# Power.net
KiCad netlist of a schematic drawn in Altium Designer
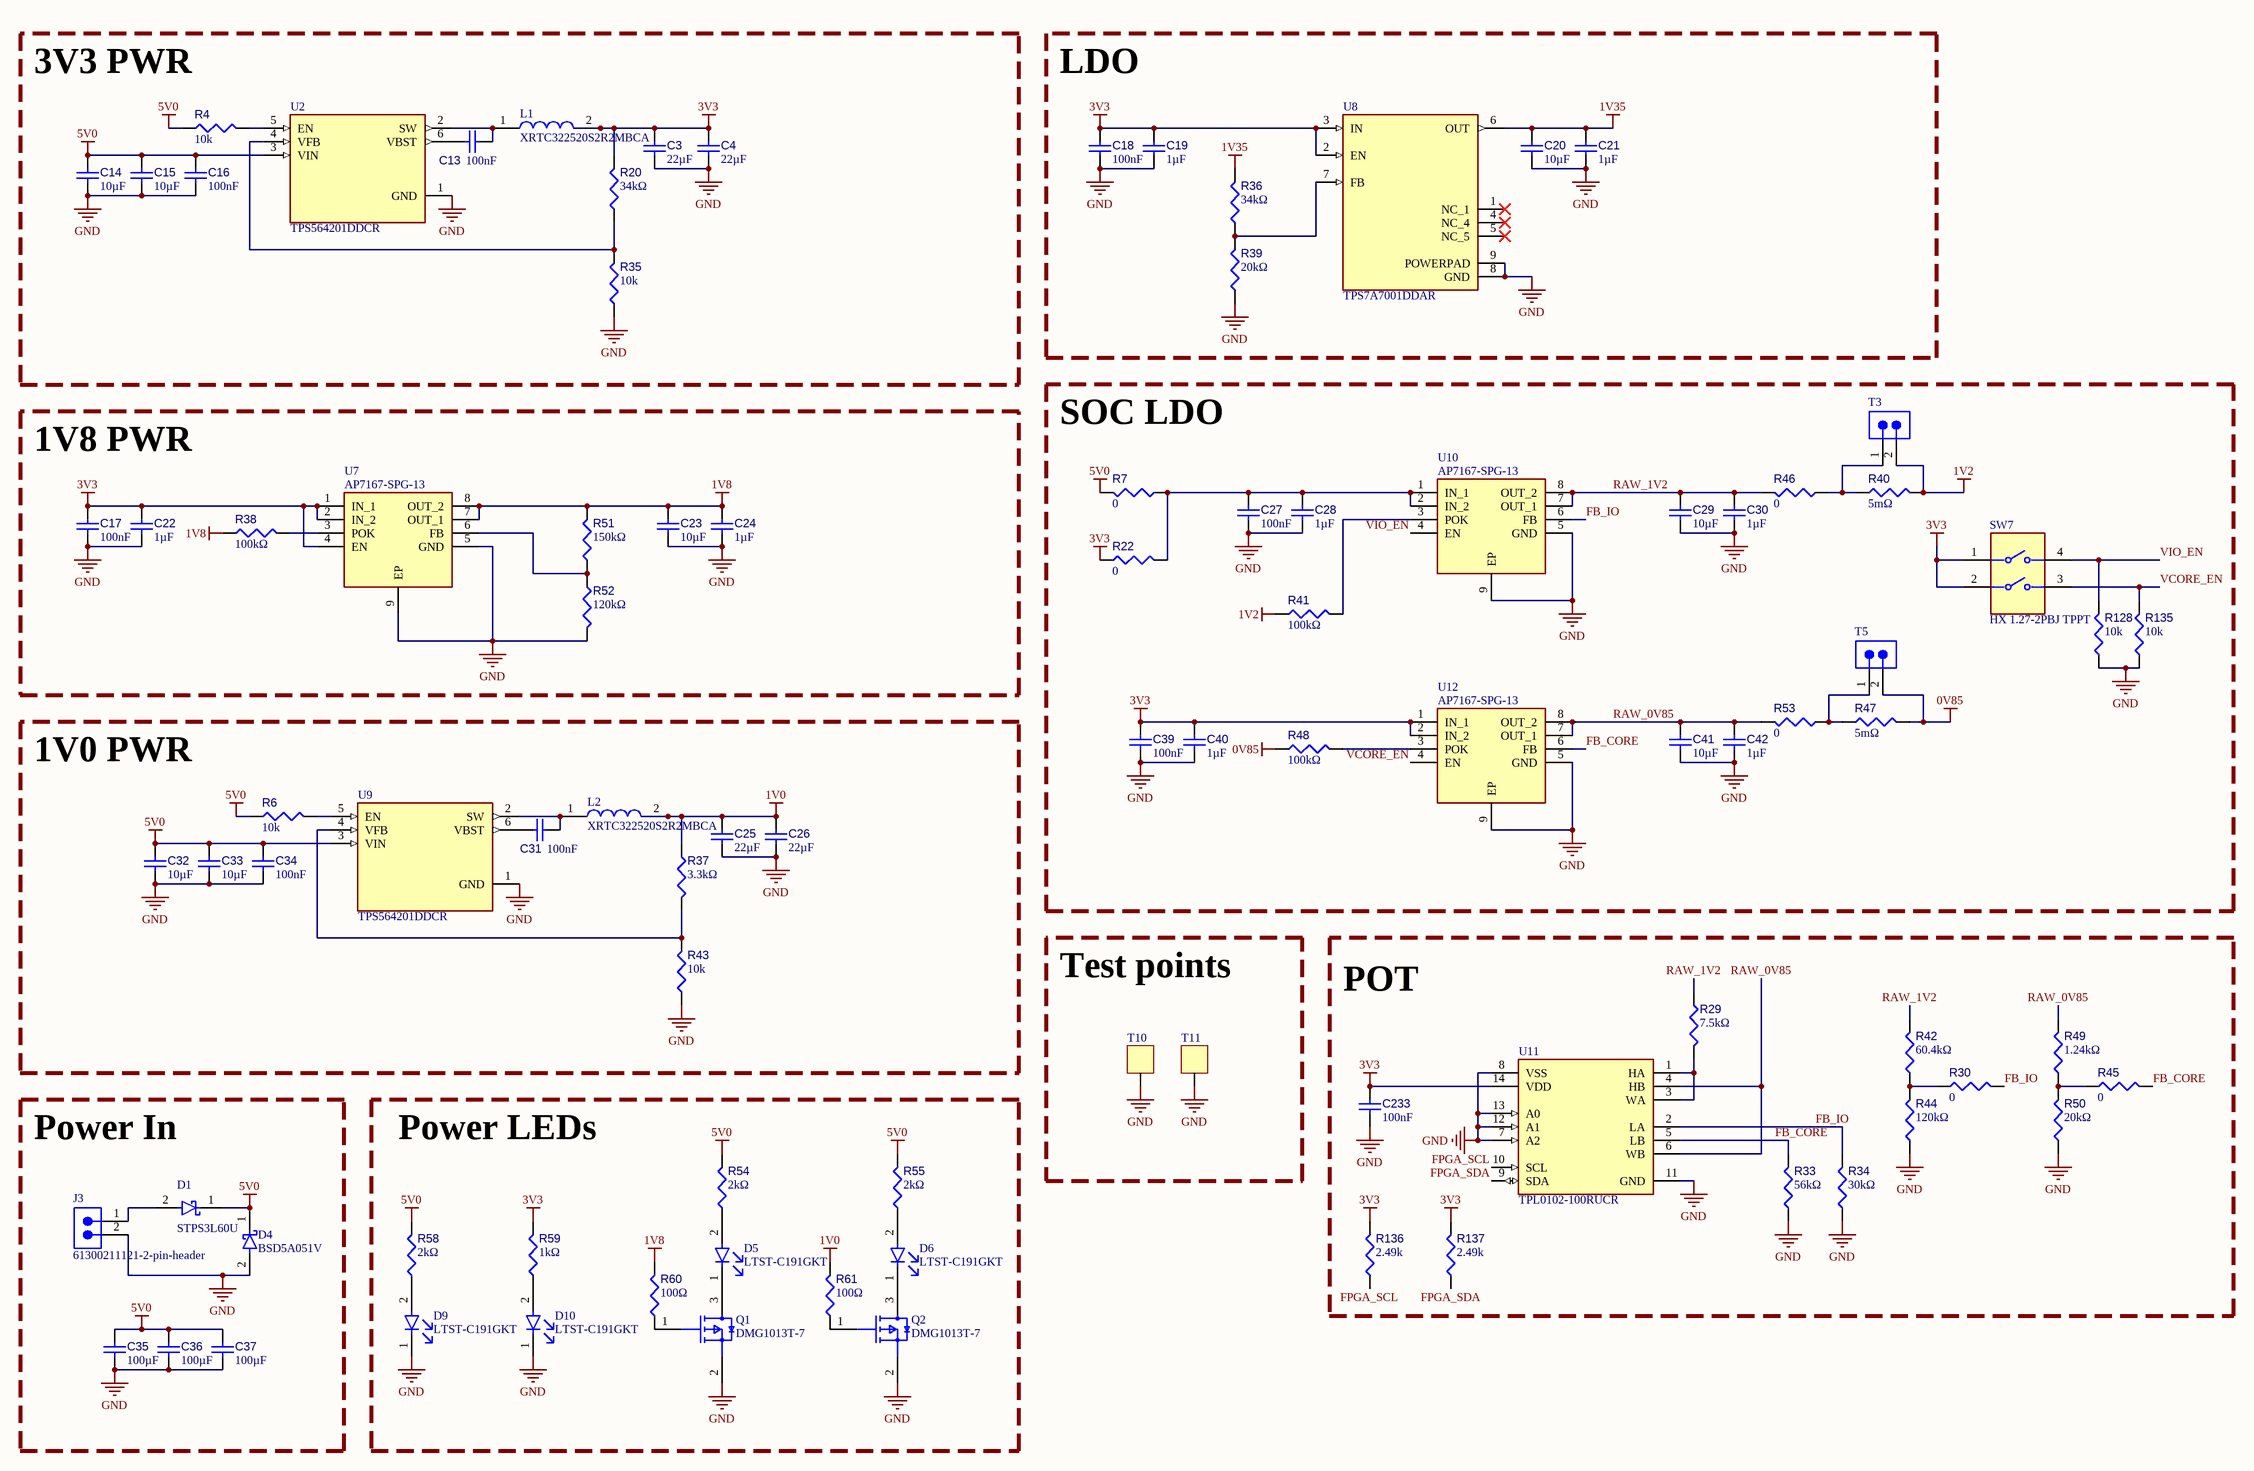
[diagram p0: Power.SchDoc]

(export (version "E")
  (design (tool "Eeschema 10.0.6"))
  (components
    (comp (ref "C3")
      (value "22µF")
      (footprint "CAP-0603-MFG")
      (description "0603-22u-20%-16V-X5R")
      (fields (field (name "TOLERANCE") "20%") (field (name "MANUFACTURER PART NUMBER") "CL10A226MO7JZNC"))
      (libsource (lib "UC Berkeley – EE194") (part "CAP-NP-2P"))
    )
    (comp (ref "C4")
      (value "22µF")
      (footprint "CAP-0603-MFG")
      (description "0603-22u-20%-16V-X5R")
      (fields (field (name "TOLERANCE") "20%") (field (name "MANUFACTURER PART NUMBER") "CL10A226MO7JZNC"))
      (libsource (lib "UC Berkeley – EE194") (part "CAP-NP-2P"))
    )
    (comp (ref "C13")
      (value "100nF")
      (footprint "CAP-0402-MFG")
      (description "0402-100n-10%-25V-X7R-AECQ200")
      (fields (field (name "TOLERANCE") "10%") (field (name "MANUFACTURER PART NUMBER") "CL05B104KA54PNC"))
      (libsource (lib "UC Berkeley – EE194") (part "CAP-NP-2P"))
    )
    (comp (ref "C14")
      (value "10µF")
      (footprint "CAP-0402-MFG")
      (description "0402-10u-20%-10V-X5R")
      (fields (field (name "TOLERANCE") "20%") (field (name "MANUFACTURER PART NUMBER") "CL05A106MP5NUNC"))
      (libsource (lib "UC Berkeley – EE194") (part "CAP-NP-2P"))
    )
    (comp (ref "C15")
      (value "10µF")
      (footprint "CAP-0402-MFG")
      (description "0402-10u-20%-10V-X5R")
      (fields (field (name "TOLERANCE") "20%") (field (name "MANUFACTURER PART NUMBER") "CL05A106MP5NUNC"))
      (libsource (lib "UC Berkeley – EE194") (part "CAP-NP-2P"))
    )
    (comp (ref "C16")
      (value "100nF")
      (footprint "CAP-0402-MFG")
      (description "0402-100n-10%-25V-X7R-AECQ200")
      (fields (field (name "TOLERANCE") "10%") (field (name "MANUFACTURER PART NUMBER") "CL05B104KA54PNC"))
      (libsource (lib "UC Berkeley – EE194") (part "CAP-NP-2P"))
    )
    (comp (ref "C17")
      (value "100nF")
      (footprint "CAP-0402-MFG")
      (description "0402-100n-10%-25V-X7R-AECQ200")
      (fields (field (name "TOLERANCE") "10%") (field (name "MANUFACTURER PART NUMBER") "CL05B104KA54PNC"))
      (libsource (lib "UC Berkeley – EE194") (part "CAP-NP-2P"))
    )
    (comp (ref "C18")
      (value "100nF")
      (footprint "CAP-0402-MFG")
      (description "0402-100n-10%-25V-X7R-AECQ200")
      (fields (field (name "TOLERANCE") "10%") (field (name "MANUFACTURER PART NUMBER") "CL05B104KA54PNC"))
      (libsource (lib "UC Berkeley – EE194") (part "CAP-NP-2P"))
    )
    (comp (ref "C19")
      (value "1µF")
      (footprint "CAP-0402-MFG")
      (description "0402-1u-10%-16V-X6S-AECQ200")
      (fields (field (name "MANUFACTURER PART NUMBER") "GRT155C81C105KE13J") (field (name "TOLERANCE") "10%"))
      (libsource (lib "UC Berkeley – EE194") (part "CAP-NP-2P"))
    )
    (comp (ref "C20")
      (value "10µF")
      (footprint "CAP-0402-MFG")
      (description "0402-10u-20%-10V-X5R")
      (fields (field (name "TOLERANCE") "20%") (field (name "MANUFACTURER PART NUMBER") "CL05A106MP5NUNC"))
      (libsource (lib "UC Berkeley – EE194") (part "CAP-NP-2P"))
    )
    (comp (ref "C21")
      (value "1µF")
      (footprint "CAP-0402-MFG")
      (description "0402-1u-10%-16V-X6S-AECQ200")
      (fields (field (name "MANUFACTURER PART NUMBER") "GRT155C81C105KE13J") (field (name "TOLERANCE") "10%"))
      (libsource (lib "UC Berkeley – EE194") (part "CAP-NP-2P"))
    )
    (comp (ref "C22")
      (value "1µF")
      (footprint "CAP-0402-MFG")
      (description "0402-1u-10%-16V-X6S-AECQ200")
      (fields (field (name "MANUFACTURER PART NUMBER") "GRT155C81C105KE13J") (field (name "TOLERANCE") "10%"))
      (libsource (lib "UC Berkeley – EE194") (part "CAP-NP-2P"))
    )
    (comp (ref "C23")
      (value "10µF")
      (footprint "CAP-0402-MFG")
      (description "0402-10u-20%-10V-X5R")
      (fields (field (name "TOLERANCE") "20%") (field (name "MANUFACTURER PART NUMBER") "CL05A106MP5NUNC"))
      (libsource (lib "UC Berkeley – EE194") (part "CAP-NP-2P"))
    )
    (comp (ref "C24")
      (value "1µF")
      (footprint "CAP-0402-MFG")
      (description "0402-1u-10%-16V-X6S-AECQ200")
      (fields (field (name "MANUFACTURER PART NUMBER") "GRT155C81C105KE13J") (field (name "TOLERANCE") "10%"))
      (libsource (lib "UC Berkeley – EE194") (part "CAP-NP-2P"))
    )
    (comp (ref "C25")
      (value "22µF")
      (footprint "CAP-0603-MFG")
      (description "0603-22u-20%-16V-X5R")
      (fields (field (name "TOLERANCE") "20%") (field (name "MANUFACTURER PART NUMBER") "CL10A226MO7JZNC"))
      (libsource (lib "UC Berkeley – EE194") (part "CAP-NP-2P"))
    )
    (comp (ref "C26")
      (value "22µF")
      (footprint "CAP-0603-MFG")
      (description "0603-22u-20%-16V-X5R")
      (fields (field (name "TOLERANCE") "20%") (field (name "MANUFACTURER PART NUMBER") "CL10A226MO7JZNC"))
      (libsource (lib "UC Berkeley – EE194") (part "CAP-NP-2P"))
    )
    (comp (ref "C27")
      (value "100nF")
      (footprint "CAP-0402-MFG")
      (description "0402-100n-10%-25V-X7R-AECQ200")
      (fields (field (name "TOLERANCE") "10%") (field (name "MANUFACTURER PART NUMBER") "CL05B104KA54PNC"))
      (libsource (lib "UC Berkeley – EE194") (part "CAP-NP-2P"))
    )
    (comp (ref "C28")
      (value "1µF")
      (footprint "CAP-0402-MFG")
      (description "0402-1u-10%-16V-X6S-AECQ200")
      (fields (field (name "MANUFACTURER PART NUMBER") "GRT155C81C105KE13J") (field (name "TOLERANCE") "10%"))
      (libsource (lib "UC Berkeley – EE194") (part "CAP-NP-2P"))
    )
    (comp (ref "C29")
      (value "10µF")
      (footprint "CAP-0402-MFG")
      (description "0402-10u-20%-10V-X5R")
      (fields (field (name "TOLERANCE") "20%") (field (name "MANUFACTURER PART NUMBER") "CL05A106MP5NUNC"))
      (libsource (lib "UC Berkeley – EE194") (part "CAP-NP-2P"))
    )
    (comp (ref "C30")
      (value "1µF")
      (footprint "CAP-0402-MFG")
      (description "0402-1u-10%-16V-X6S-AECQ200")
      (fields (field (name "MANUFACTURER PART NUMBER") "GRT155C81C105KE13J") (field (name "TOLERANCE") "10%"))
      (libsource (lib "UC Berkeley – EE194") (part "CAP-NP-2P"))
    )
    (comp (ref "C31")
      (value "100nF")
      (footprint "CAP-0402-MFG")
      (description "0402-100n-10%-25V-X7R-AECQ200")
      (fields (field (name "TOLERANCE") "10%") (field (name "MANUFACTURER PART NUMBER") "CL05B104KA54PNC"))
      (libsource (lib "UC Berkeley – EE194") (part "CAP-NP-2P"))
    )
    (comp (ref "C32")
      (value "10µF")
      (footprint "CAP-0402-MFG")
      (description "0402-10u-20%-10V-X5R")
      (fields (field (name "TOLERANCE") "20%") (field (name "MANUFACTURER PART NUMBER") "CL05A106MP5NUNC"))
      (libsource (lib "UC Berkeley – EE194") (part "CAP-NP-2P"))
    )
    (comp (ref "C33")
      (value "10µF")
      (footprint "CAP-0402-MFG")
      (description "0402-10u-20%-10V-X5R")
      (fields (field (name "TOLERANCE") "20%") (field (name "MANUFACTURER PART NUMBER") "CL05A106MP5NUNC"))
      (libsource (lib "UC Berkeley – EE194") (part "CAP-NP-2P"))
    )
    (comp (ref "C34")
      (value "100nF")
      (footprint "CAP-0402-MFG")
      (description "0402-100n-10%-25V-X7R-AECQ200")
      (fields (field (name "TOLERANCE") "10%") (field (name "MANUFACTURER PART NUMBER") "CL05B104KA54PNC"))
      (libsource (lib "UC Berkeley – EE194") (part "CAP-NP-2P"))
    )
    (comp (ref "C35")
      (value "100µF")
      (footprint "CAP-0805-MFG")
      (description "0805-100u-20%-6.3V-X5R")
      (fields (field (name "MANUFACTURER PART NUMBER") "GRM21BR60J107ME15L") (field (name "TOLERANCE") "20%"))
      (libsource (lib "UC Berkeley – EE194") (part "CAP-NP-2P"))
    )
    (comp (ref "C36")
      (value "100µF")
      (footprint "CAP-0805-MFG")
      (description "0805-100u-20%-6.3V-X5R")
      (fields (field (name "MANUFACTURER PART NUMBER") "GRM21BR60J107ME15L") (field (name "TOLERANCE") "20%"))
      (libsource (lib "UC Berkeley – EE194") (part "CAP-NP-2P"))
    )
    (comp (ref "C37")
      (value "100µF")
      (footprint "CAP-0805-MFG")
      (description "0805-100u-20%-6.3V-X5R")
      (fields (field (name "MANUFACTURER PART NUMBER") "GRM21BR60J107ME15L") (field (name "TOLERANCE") "20%"))
      (libsource (lib "UC Berkeley – EE194") (part "CAP-NP-2P"))
    )
    (comp (ref "C39")
      (value "100nF")
      (footprint "CAP-0402-MFG")
      (description "0402-100n-10%-25V-X7R-AECQ200")
      (fields (field (name "TOLERANCE") "10%") (field (name "MANUFACTURER PART NUMBER") "CL05B104KA54PNC"))
      (libsource (lib "UC Berkeley – EE194") (part "CAP-NP-2P"))
    )
    (comp (ref "C40")
      (value "1µF")
      (footprint "CAP-0402-MFG")
      (description "0402-1u-10%-16V-X6S-AECQ200")
      (fields (field (name "MANUFACTURER PART NUMBER") "GRT155C81C105KE13J") (field (name "TOLERANCE") "10%"))
      (libsource (lib "UC Berkeley – EE194") (part "CAP-NP-2P"))
    )
    (comp (ref "C41")
      (value "10µF")
      (footprint "CAP-0402-MFG")
      (description "0402-10u-20%-10V-X5R")
      (fields (field (name "TOLERANCE") "20%") (field (name "MANUFACTURER PART NUMBER") "CL05A106MP5NUNC"))
      (libsource (lib "UC Berkeley – EE194") (part "CAP-NP-2P"))
    )
    (comp (ref "C42")
      (value "1µF")
      (footprint "CAP-0402-MFG")
      (description "0402-1u-10%-16V-X6S-AECQ200")
      (fields (field (name "MANUFACTURER PART NUMBER") "GRT155C81C105KE13J") (field (name "TOLERANCE") "10%"))
      (libsource (lib "UC Berkeley – EE194") (part "CAP-NP-2P"))
    )
    (comp (ref "C233")
      (value "100nF")
      (footprint "CAP-0402-MFG")
      (description "0402-100n-10%-25V-X7R-AECQ200")
      (fields (field (name "TOLERANCE") "10%") (field (name "MANUFACTURER PART NUMBER") "CL05B104KA54PNC"))
      (libsource (lib "UC Berkeley – EE194") (part "CAP-NP-2P"))
    )
    (comp (ref "D1")
      (value "STPS3L60U")
      (footprint "FP-DO214AA-MFG")
      (description "DO214AA-UNI-SCHOTTKY-60V-3A-590mV")
      (libsource (lib "UC Berkeley – EE194") (part "SCHOTTKY-UNI-2P-DIODE"))
    )
    (comp (ref "D4")
      (value "BSD5A051V")
      (footprint "SOD-523")
      (description "TVS ESD protection clamp generic")
      (fields (field (name "SOURCE") "BWRC.SchLib"))
      (libsource (lib "UC Berkeley – EE194") (part "SCHOTTKY-UNI-2P-DIODE"))
    )
    (comp (ref "D5")
      (value "LTST-C191GKT")
      (footprint "LED-0603-MFG")
      (description "LED yellow green 0603 wavelength 569nm light intensity 12mcd Front Mounting")
      (libsource (lib "UC Berkeley – EE194") (part "LED"))
    )
    (comp (ref "D6")
      (value "LTST-C191GKT")
      (footprint "LED-0603-MFG")
      (description "LED yellow green 0603 wavelength 569nm light intensity 12mcd Front Mounting")
      (libsource (lib "UC Berkeley – EE194") (part "LED"))
    )
    (comp (ref "D9")
      (value "LTST-C191GKT")
      (footprint "LED-0603-MFG")
      (description "LED yellow green 0603 wavelength 569nm light intensity 12mcd Front Mounting")
      (libsource (lib "UC Berkeley – EE194") (part "LED"))
    )
    (comp (ref "D10")
      (value "LTST-C191GKT")
      (footprint "LED-0603-MFG")
      (description "LED yellow green 0603 wavelength 569nm light intensity 12mcd Front Mounting")
      (libsource (lib "UC Berkeley – EE194") (part "LED"))
    )
    (comp (ref "J3")
      (value "61300211121-2-pin-header")
      (footprint "61300211121")
      (fields (field (name "MANUFACTURER PART NUMBER") "61300211121"))
      (libsource (lib "UC Berkeley – EE194") (part "Header_Male_1R_02P"))
    )
    (comp (ref "L1")
      (value "XRTC322520S2R2MBCA")
      (footprint "INDC2520X100N")
      (description "Ind,3.2x2.5x1mm,2.2uH?20%,4A,shd")
      (libsource (lib "UC Berkeley – EE194") (part "XRTC322520S2R2MBCA"))
    )
    (comp (ref "L2")
      (value "XRTC322520S2R2MBCA")
      (footprint "INDC2520X100N")
      (description "Ind,3.2x2.5x1mm,2.2uH?20%,4A,shd")
      (libsource (lib "UC Berkeley – EE194") (part "XRTC322520S2R2MBCA"))
    )
    (comp (ref "Q1")
      (value "DMG1013T-7")
      (footprint "FP-SOT523-MFG")
      (description "P-Channel 20 V 0.7 Ohm 0.27 W Enhancement Mode Mosfet - SOT-523")
      (libsource (lib "UC Berkeley – EE194") (part "P-MOSFET-3P"))
    )
    (comp (ref "Q2")
      (value "DMG1013T-7")
      (footprint "FP-SOT523-MFG")
      (description "P-Channel 20 V 0.7 Ohm 0.27 W Enhancement Mode Mosfet - SOT-523")
      (libsource (lib "UC Berkeley – EE194") (part "P-MOSFET-3P"))
    )
    (comp (ref "R4")
      (value "10k")
      (footprint "RES-0402")
      (description "0402-10k-1%-1/16W-AEC-Q200")
      (fields (field (name "POWER") "63mW") (field (name "TOLERANCE") "1%"))
      (libsource (lib "UC Berkeley – EE194") (part "RES-2P"))
    )
    (comp (ref "R6")
      (value "10k")
      (footprint "RES-0402")
      (description "0402-10k-1%-1/16W-AEC-Q200")
      (fields (field (name "POWER") "63mW") (field (name "TOLERANCE") "1%"))
      (libsource (lib "UC Berkeley – EE194") (part "RES-2P"))
    )
    (comp (ref "R7")
      (value "0")
      (footprint "RES-0402")
      (description "0402-0-1A-AEC-Q200")
      (fields (field (name "MANUFACTURER PART NUMBER") "AC0402JR-130RL"))
      (libsource (lib "UC Berkeley – EE194") (part "RES-2P"))
    )
    (comp (ref "R20")
      (value "34kΩ")
      (footprint "RES-0402")
      (description "0402-34k-1%-1/16W-AEC-Q200")
      (fields (field (name "TOLERANCE") "1%") (field (name "POWER") "63mW"))
      (libsource (lib "UC Berkeley – EE194") (part "RES-2P"))
    )
    (comp (ref "R22")
      (value "0")
      (footprint "RES-0402")
      (description "0402-0-1A-AEC-Q200")
      (fields (field (name "MANUFACTURER PART NUMBER") "AC0402JR-130RL"))
      (libsource (lib "UC Berkeley – EE194") (part "RES-2P"))
    )
    (comp (ref "R29")
      (value "7.5kΩ")
      (footprint "RES-0402")
      (description "0402-7.5k-1%-1/16W-AEC-Q200")
      (fields (field (name "TOLERANCE") "1%") (field (name "MANUFACTURER PART NUMBER") "CRCW04027K50FKED"))
      (libsource (lib "UC Berkeley – EE194") (part "RES-2P"))
    )
    (comp (ref "R30")
      (value "0")
      (footprint "RES-0402")
      (description "0402-0-1A-AEC-Q200")
      (fields (field (name "MANUFACTURER PART NUMBER") "AC0402JR-130RL"))
      (libsource (lib "UC Berkeley – EE194") (part "RES-2P"))
    )
    (comp (ref "R33")
      (value "56kΩ")
      (footprint "RES-0402")
      (description "0402-56k-1%-1/16W-AEC-Q200")
      (fields (field (name "TOLERANCE") "1%") (field (name "MANUFACTURER PART NUMBER") "AF0402FR-0756KL"))
      (libsource (lib "UC Berkeley – EE194") (part "RES-2P"))
    )
    (comp (ref "R34")
      (value "30kΩ")
      (footprint "RES-0402")
      (description "0402-30k-1%-1/16W-AEC-Q200")
      (fields (field (name "TOLERANCE") "1%") (field (name "POWER") "63mW"))
      (libsource (lib "UC Berkeley – EE194") (part "RES-2P"))
    )
    (comp (ref "R35")
      (value "10k")
      (footprint "RES-0402")
      (description "0402-10k-1%-1/16W-AEC-Q200")
      (fields (field (name "POWER") "63mW") (field (name "TOLERANCE") "1%"))
      (libsource (lib "UC Berkeley – EE194") (part "RES-2P"))
    )
    (comp (ref "R36")
      (value "34kΩ")
      (footprint "RES-0402")
      (description "0402-34k-1%-1/16W-AEC-Q200")
      (fields (field (name "TOLERANCE") "1%") (field (name "POWER") "63mW"))
      (libsource (lib "UC Berkeley – EE194") (part "RES-2P"))
    )
    (comp (ref "R37")
      (value "3.3kΩ")
      (footprint "RES-0402")
      (description "0402-3.3k-1%-1/16W-AEC-Q200")
      (fields (field (name "POWER") "63mW") (field (name "TOLERANCE") "1%"))
      (libsource (lib "UC Berkeley – EE194") (part "RES-2P"))
    )
    (comp (ref "R38")
      (value "100kΩ")
      (footprint "RES-0402")
      (description "0402-100k-1%-1/16W-AEC-Q200")
      (fields (field (name "MANUFACTURER PART NUMBER") "AC0402FR-07100KL") (field (name "TOLERANCE") "1%"))
      (libsource (lib "UC Berkeley – EE194") (part "RES-2P"))
    )
    (comp (ref "R39")
      (value "20kΩ")
      (footprint "RES-0402")
      (description "0402-20k-1%-1/16W-AEC-Q200")
      (fields (field (name "TOLERANCE") "1%") (field (name "MANUFACTURER PART NUMBER") "AC0402FR-0720KL"))
      (libsource (lib "UC Berkeley – EE194") (part "RES-2P"))
    )
    (comp (ref "R40")
      (value "5mΩ")
      (footprint "RES-0603-MFG")
      (description "0603-5m-1%-0.5W-AECQ200")
      (fields (field (name "TOLERANCE") "1%") (field (name "MANUFACTURER PART NUMBER") "PA0603FRE570R005L"))
      (libsource (lib "UC Berkeley – EE194") (part "RES-2P"))
    )
    (comp (ref "R41")
      (value "100kΩ")
      (footprint "RES-0402")
      (description "0402-100k-1%-1/16W-AEC-Q200")
      (fields (field (name "MANUFACTURER PART NUMBER") "AC0402FR-07100KL") (field (name "TOLERANCE") "1%"))
      (libsource (lib "UC Berkeley – EE194") (part "RES-2P"))
    )
    (comp (ref "R42")
      (value "60.4kΩ")
      (footprint "RES-0402")
      (description "0402-60.4k-1%-1/16W-AEC-Q200")
      (fields (field (name "TOLERANCE") "1%") (field (name "MANUFACTURER PART NUMBER") "AC0402FR-0760K4L"))
      (libsource (lib "UC Berkeley – EE194") (part "RES-2P"))
    )
    (comp (ref "R43")
      (value "10k")
      (footprint "RES-0402")
      (description "0402-10k-1%-1/16W-AEC-Q200")
      (fields (field (name "POWER") "63mW") (field (name "TOLERANCE") "1%"))
      (libsource (lib "UC Berkeley – EE194") (part "RES-2P"))
    )
    (comp (ref "R44")
      (value "120kΩ")
      (footprint "RES-0402")
      (description "0402-120k-1%-1/16W-AEC-Q200")
      (fields (field (name "POWER") "63mW") (field (name "MANUFACTURER PART NUMBER") "AC0402FR-07120KL"))
      (libsource (lib "UC Berkeley – EE194") (part "RES-2P"))
    )
    (comp (ref "R45")
      (value "0")
      (footprint "RES-0402")
      (description "0402-0-1A-AEC-Q200")
      (fields (field (name "MANUFACTURER PART NUMBER") "AC0402JR-130RL"))
      (libsource (lib "UC Berkeley – EE194") (part "RES-2P"))
    )
    (comp (ref "R46")
      (value "0")
      (footprint "RES-0603-MFG")
      (description "0603-0-1A-AECQ200")
      (fields (field (name "MANUFACTURER PART NUMBER") "AC0603FR-070RL") (field (name "TOLERANCE") "1%"))
      (libsource (lib "UC Berkeley – EE194") (part "RES-2P"))
    )
    (comp (ref "R47")
      (value "5mΩ")
      (footprint "RES-0603-MFG")
      (description "0603-5m-1%-0.5W-AECQ200")
      (fields (field (name "TOLERANCE") "1%") (field (name "MANUFACTURER PART NUMBER") "PA0603FRE570R005L"))
      (libsource (lib "UC Berkeley – EE194") (part "RES-2P"))
    )
    (comp (ref "R48")
      (value "100kΩ")
      (footprint "RES-0402")
      (description "0402-100k-1%-1/16W-AEC-Q200")
      (fields (field (name "MANUFACTURER PART NUMBER") "AC0402FR-07100KL") (field (name "TOLERANCE") "1%"))
      (libsource (lib "UC Berkeley – EE194") (part "RES-2P"))
    )
    (comp (ref "R49")
      (value "1.24kΩ")
      (footprint "RES-0402")
      (description "0402-1.24k-1%-1/16W-AEC-Q200")
      (fields (field (name "POWER") "63mW") (field (name "TOLERANCE") "1%"))
      (libsource (lib "UC Berkeley – EE194") (part "RES-2P"))
    )
    (comp (ref "R50")
      (value "20kΩ")
      (footprint "RES-0402")
      (description "0402-20k-1%-1/16W-AEC-Q200")
      (fields (field (name "MANUFACTURER PART NUMBER") "AC0402FR-0720KL") (field (name "TOLERANCE") "1%"))
      (libsource (lib "UC Berkeley – EE194") (part "RES-2P"))
    )
    (comp (ref "R51")
      (value "150kΩ")
      (footprint "RES-0402")
      (description "0402-150k-1%-1/16W-AEC-Q200")
      (fields (field (name "POWER") "63mW") (field (name "TOLERANCE") "1%"))
      (libsource (lib "UC Berkeley – EE194") (part "RES-2P"))
    )
    (comp (ref "R52")
      (value "120kΩ")
      (footprint "RES-0402")
      (description "0402-120k-1%-1/16W-AEC-Q200")
      (fields (field (name "POWER") "63mW") (field (name "MANUFACTURER PART NUMBER") "AC0402FR-07120KL"))
      (libsource (lib "UC Berkeley – EE194") (part "RES-2P"))
    )
    (comp (ref "R53")
      (value "0")
      (footprint "RES-0603-MFG")
      (description "0603-0-1A-AECQ200")
      (fields (field (name "MANUFACTURER PART NUMBER") "AC0603FR-070RL") (field (name "TOLERANCE") "1%"))
      (libsource (lib "UC Berkeley – EE194") (part "RES-2P"))
    )
    (comp (ref "R54")
      (value "2kΩ")
      (footprint "RES-0402")
      (description "0402-2k-1%-1/16W-AEC-Q200")
      (fields (field (name "TOLERANCE") "1%") (field (name "POWER") "63mW"))
      (libsource (lib "UC Berkeley – EE194") (part "RES-2P"))
    )
    (comp (ref "R55")
      (value "2kΩ")
      (footprint "RES-0402")
      (description "0402-2k-1%-1/16W-AEC-Q200")
      (fields (field (name "TOLERANCE") "1%") (field (name "POWER") "63mW"))
      (libsource (lib "UC Berkeley – EE194") (part "RES-2P"))
    )
    (comp (ref "R58")
      (value "2kΩ")
      (footprint "RES-0402")
      (description "0402-2k-1%-1/16W-AEC-Q200")
      (fields (field (name "TOLERANCE") "1%") (field (name "POWER") "63mW"))
      (libsource (lib "UC Berkeley – EE194") (part "RES-2P"))
    )
    (comp (ref "R59")
      (value "1kΩ")
      (footprint "RES-0402")
      (description "0402-1k-1%-1/16W-AEC-Q200")
      (fields (field (name "MANUFACTURER PART NUMBER") "AC0402FR-071KL") (field (name "POWER") "63mW"))
      (libsource (lib "UC Berkeley – EE194") (part "RES-2P"))
    )
    (comp (ref "R60")
      (value "100Ω")
      (footprint "RES-0402")
      (description "0402-100-1%-1/16W-AEC-Q200")
      (fields (field (name "MANUFACTURER PART NUMBER") "AC0402FR-07100RL") (field (name "POWER") "63mW"))
      (libsource (lib "UC Berkeley – EE194") (part "RES-2P"))
    )
    (comp (ref "R61")
      (value "100Ω")
      (footprint "RES-0402")
      (description "0402-100-1%-1/16W-AEC-Q200")
      (fields (field (name "MANUFACTURER PART NUMBER") "AC0402FR-07100RL") (field (name "POWER") "63mW"))
      (libsource (lib "UC Berkeley – EE194") (part "RES-2P"))
    )
    (comp (ref "R128")
      (value "10k")
      (footprint "RES-0402")
      (description "0402-10k-1%-1/16W-AEC-Q200")
      (fields (field (name "TOLERANCE") "1%") (field (name "MANUFACTURER PART NUMBER") "AC0402FR-0710KL"))
      (libsource (lib "UC Berkeley – EE194") (part "RES-2P"))
    )
    (comp (ref "R135")
      (value "10k")
      (footprint "RES-0402")
      (description "0402-10k-1%-1/16W-AEC-Q200")
      (fields (field (name "TOLERANCE") "1%") (field (name "MANUFACTURER PART NUMBER") "AC0402FR-0710KL"))
      (libsource (lib "UC Berkeley – EE194") (part "RES-2P"))
    )
    (comp (ref "R136")
      (value "2.49k")
      (footprint "RES-0402")
      (description "0402-2.49k-1%-1/16W-AECQ200")
      (fields (field (name "TOLERANCE") "1%") (field (name "MANUFACTURER PART NUMBER") "AC0402FR-072K49L"))
      (libsource (lib "UC Berkeley – EE194") (part "RES-2P"))
    )
    (comp (ref "R137")
      (value "2.49k")
      (footprint "RES-0402")
      (description "0402-2.49k-1%-1/16W-AECQ200")
      (fields (field (name "TOLERANCE") "1%") (field (name "MANUFACTURER PART NUMBER") "AC0402FR-072K49L"))
      (libsource (lib "UC Berkeley – EE194") (part "RES-2P"))
    )
    (comp (ref "SW7")
      (value "HX 1.27-2PBJ TPPT")
      (footprint "HX 1.27-2PBJ TPPT-Footprint-1")
      (description "Dual 1.27mm SMT DIP Switch")
      (libsource (lib "UC Berkeley – EE194") (part "HX 1.27-2PBJ TPPT-Symbol-1"))
    )
    (comp (ref "T3")
      (value "61300211121-2-pin-header")
      (footprint "61300211121")
      (fields (field (name "MANUFACTURER PART NUMBER") "61300211121"))
      (libsource (lib "UC Berkeley – EE194") (part "Header_Male_1R_02P"))
    )
    (comp (ref "T5")
      (value "61300211121-2-pin-header")
      (footprint "61300211121")
      (fields (field (name "MANUFACTURER PART NUMBER") "61300211121"))
      (libsource (lib "UC Berkeley – EE194") (part "Header_Male_1R_02P"))
    )
    (comp (ref "T10")
      (value "TEST_PT")
      (footprint "TP-100X100/ROUND-THT")
      (description "Test point 1 pin")
      (fields (field (name "SOURCE") "BWRC.SchLib"))
      (libsource (lib "UC Berkeley – EE194") (part "TEST_PT"))
    )
    (comp (ref "T11")
      (value "TEST_PT")
      (footprint "TP-100X100/ROUND-THT")
      (description "Test point 1 pin")
      (fields (field (name "SOURCE") "BWRC.SchLib"))
      (libsource (lib "UC Berkeley – EE194") (part "TEST_PT"))
    )
    (comp (ref "U2")
      (value "TPS564201DDCR")
      (footprint "SOT95P280X110-6N")
      (libsource (lib "UC Berkeley – EE194") (part "TPS564201DDCR"))
    )
    (comp (ref "U7")
      (value "AP7167-SPG-13")
      (footprint "SOIC127P600X175-9N")
      (description "AP7167 Series 5.5 V 1.2 A Low Dropout Regulator with Pok - SOP-8EP")
      (libsource (lib "UC Berkeley – EE194") (part "AP7167-SPG-13"))
    )
    (comp (ref "U8")
      (value "TPS7A7001DDAR")
      (footprint "VREG_TPS7A7001DDAR")
      (description "2-A, adjustable ultra-low-dropout voltage regulator with enable")
      (libsource (lib "UC Berkeley – EE194") (part "TPS7A7001DDAR"))
    )
    (comp (ref "U9")
      (value "TPS564201DDCR")
      (footprint "SOT95P280X110-6N")
      (libsource (lib "UC Berkeley – EE194") (part "TPS564201DDCR"))
    )
    (comp (ref "U10")
      (value "AP7167-SPG-13")
      (footprint "SOIC127P600X175-9N")
      (description "AP7167 Series 5.5 V 1.2 A Low Dropout Regulator with Pok - SOP-8EP")
      (libsource (lib "UC Berkeley – EE194") (part "AP7167-SPG-13"))
    )
    (comp (ref "U11")
      (value "TPL0102-100RUCR")
      (footprint "FP-RUC0014A-IPC_B")
      (description "Digital Potentiometer 100kOhm 256POS Non-Volatile Linear 14-Pin X2QFN T/R")
      (fields (field (name "TOLERANCE") "20%"))
      (libsource (lib "UC Berkeley – EE194") (part "TPL0102-100RUCR"))
    )
    (comp (ref "U12")
      (value "AP7167-SPG-13")
      (footprint "SOIC127P600X175-9N")
      (description "AP7167 Series 5.5 V 1.2 A Low Dropout Regulator with Pok - SOP-8EP")
      (libsource (lib "UC Berkeley – EE194") (part "AP7167-SPG-13"))
    )
  )
  (nets
    (net (code "1") (name "/FB_CORE") (class "Default")
      (node (ref "R33") (pin "2") (pinfunction "2_2") (pintype "passive"))
      (node (ref "R45") (pin "2") (pinfunction "2_2") (pintype "passive"))
      (node (ref "U11") (pin "5") (pinfunction "LB_5") (pintype "passive"))
      (node (ref "U12") (pin "6") (pinfunction "FB_6") (pintype "passive"))
    )
    (net (code "2") (name "/FB_IO") (class "Default")
      (node (ref "R30") (pin "2") (pinfunction "2_2") (pintype "passive"))
      (node (ref "R34") (pin "2") (pinfunction "2_2") (pintype "passive"))
      (node (ref "U10") (pin "6") (pinfunction "FB_6") (pintype "passive"))
      (node (ref "U11") (pin "2") (pinfunction "LA_2") (pintype "passive"))
    )
    (net (code "3") (name "/FPGA_SCL") (class "Default")
      (node (ref "R136") (pin "1") (pinfunction "1_1") (pintype "passive"))
      (node (ref "U11") (pin "10") (pinfunction "SCL_10") (pintype "input"))
    )
    (net (code "4") (name "/FPGA_SDA") (class "Default")
      (node (ref "R137") (pin "1") (pinfunction "1_1") (pintype "passive"))
      (node (ref "U11") (pin "9") (pinfunction "SDA_9") (pintype "bidirectional"))
    )
    (net (code "5") (name "/RAW_0V85") (class "Default")
      (node (ref "C41") (pin "1") (pinfunction "1_1") (pintype "passive"))
      (node (ref "C42") (pin "1") (pinfunction "1_1") (pintype "passive"))
      (node (ref "R49") (pin "2") (pinfunction "2_2") (pintype "passive"))
      (node (ref "R53") (pin "2") (pinfunction "2_2") (pintype "passive"))
      (node (ref "U11") (pin "4") (pinfunction "HB_4") (pintype "passive"))
      (node (ref "U11") (pin "6") (pinfunction "WB_6") (pintype "passive"))
      (node (ref "U12") (pin "7") (pinfunction "OUT_1_7") (pintype "passive"))
      (node (ref "U12") (pin "8") (pinfunction "OUT_2_8") (pintype "passive"))
    )
    (net (code "6") (name "/RAW_1V2") (class "Default")
      (node (ref "C29") (pin "1") (pinfunction "1_1") (pintype "passive"))
      (node (ref "C30") (pin "1") (pinfunction "1_1") (pintype "passive"))
      (node (ref "R29") (pin "1") (pinfunction "1_1") (pintype "passive"))
      (node (ref "R42") (pin "2") (pinfunction "2_2") (pintype "passive"))
      (node (ref "R46") (pin "2") (pinfunction "2_2") (pintype "passive"))
      (node (ref "U10") (pin "7") (pinfunction "OUT_1_7") (pintype "passive"))
      (node (ref "U10") (pin "8") (pinfunction "OUT_2_8") (pintype "passive"))
    )
    (net (code "7") (name "/VCORE_EN") (class "Default")
      (node (ref "R135") (pin "2") (pinfunction "2_2") (pintype "passive"))
      (node (ref "SW7") (pin "3") (pinfunction "3_3") (pintype "passive"))
      (node (ref "U12") (pin "4") (pinfunction "EN_4") (pintype "passive"))
    )
    (net (code "8") (name "/VIO_EN") (class "Default")
      (node (ref "R128") (pin "2") (pinfunction "2_2") (pintype "passive"))
      (node (ref "SW7") (pin "4") (pinfunction "4_4") (pintype "passive"))
      (node (ref "U10") (pin "4") (pinfunction "EN_4") (pintype "passive"))
    )
    (net (code "9") (name "0V85") (class "Default")
      (node (ref "R47") (pin "2") (pinfunction "2_2") (pintype "passive"))
      (node (ref "R48") (pin "1") (pinfunction "1_1") (pintype "passive"))
      (node (ref "T5") (pin "2") (pinfunction "2_2") (pintype "passive"))
    )
    (net (code "10") (name "1V0") (class "Default")
      (node (ref "C25") (pin "1") (pinfunction "1_1") (pintype "passive"))
      (node (ref "C26") (pin "1") (pinfunction "1_1") (pintype "passive"))
      (node (ref "L2") (pin "2") (pinfunction "2_2") (pintype "passive"))
      (node (ref "R37") (pin "1") (pinfunction "1_1") (pintype "passive"))
      (node (ref "R61") (pin "2") (pinfunction "2_2") (pintype "passive"))
    )
    (net (code "11") (name "1V2") (class "Default")
      (node (ref "R40") (pin "2") (pinfunction "2_2") (pintype "passive"))
      (node (ref "R41") (pin "1") (pinfunction "1_1") (pintype "passive"))
      (node (ref "T3") (pin "2") (pinfunction "2_2") (pintype "passive"))
    )
    (net (code "12") (name "1V8") (class "Default")
      (node (ref "C23") (pin "1") (pinfunction "1_1") (pintype "passive"))
      (node (ref "C24") (pin "1") (pinfunction "1_1") (pintype "passive"))
      (node (ref "R38") (pin "1") (pinfunction "1_1") (pintype "passive"))
      (node (ref "R51") (pin "2") (pinfunction "2_2") (pintype "passive"))
      (node (ref "R60") (pin "2") (pinfunction "2_2") (pintype "passive"))
      (node (ref "U7") (pin "7") (pinfunction "OUT_1_7") (pintype "passive"))
      (node (ref "U7") (pin "8") (pinfunction "OUT_2_8") (pintype "passive"))
    )
    (net (code "13") (name "1V35") (class "Default")
      (node (ref "C20") (pin "2") (pinfunction "2_2") (pintype "passive"))
      (node (ref "C21") (pin "1") (pinfunction "1_1") (pintype "passive"))
      (node (ref "R36") (pin "2") (pinfunction "2_2") (pintype "passive"))
      (node (ref "U8") (pin "6") (pinfunction "OUT_6") (pintype "output"))
    )
    (net (code "14") (name "3V3") (class "Default")
      (node (ref "C17") (pin "1") (pinfunction "1_1") (pintype "passive"))
      (node (ref "C18") (pin "1") (pinfunction "1_1") (pintype "passive"))
      (node (ref "C19") (pin "1") (pinfunction "1_1") (pintype "passive"))
      (node (ref "C22") (pin "1") (pinfunction "1_1") (pintype "passive"))
      (node (ref "C233") (pin "1") (pinfunction "1_1") (pintype "passive"))
      (node (ref "C3") (pin "1") (pinfunction "1_1") (pintype "passive"))
      (node (ref "C39") (pin "1") (pinfunction "1_1") (pintype "passive"))
      (node (ref "C4") (pin "1") (pinfunction "1_1") (pintype "passive"))
      (node (ref "C40") (pin "1") (pinfunction "1_1") (pintype "passive"))
      (node (ref "L1") (pin "2") (pinfunction "2_2") (pintype "passive"))
      (node (ref "R136") (pin "2") (pinfunction "2_2") (pintype "passive"))
      (node (ref "R137") (pin "2") (pinfunction "2_2") (pintype "passive"))
      (node (ref "R20") (pin "2") (pinfunction "2_2") (pintype "passive"))
      (node (ref "R22") (pin "1") (pinfunction "1_1") (pintype "passive"))
      (node (ref "R59") (pin "2") (pinfunction "2_2") (pintype "passive"))
      (node (ref "SW7") (pin "1") (pinfunction "1_1") (pintype "passive"))
      (node (ref "SW7") (pin "2") (pinfunction "2_2") (pintype "passive"))
      (node (ref "U11") (pin "14") (pinfunction "VDD_14") (pintype "power_in"))
      (node (ref "U12") (pin "1") (pinfunction "IN_1_1") (pintype "passive"))
      (node (ref "U12") (pin "2") (pinfunction "IN_2_2") (pintype "passive"))
      (node (ref "U7") (pin "1") (pinfunction "IN_1_1") (pintype "passive"))
      (node (ref "U7") (pin "2") (pinfunction "IN_2_2") (pintype "passive"))
      (node (ref "U7") (pin "4") (pinfunction "EN_4") (pintype "passive"))
      (node (ref "U8") (pin "2") (pinfunction "EN_2") (pintype "input"))
      (node (ref "U8") (pin "3") (pinfunction "IN_3") (pintype "input"))
    )
    (net (code "15") (name "5V0") (class "Default")
      (node (ref "C14") (pin "1") (pinfunction "1_1") (pintype "passive"))
      (node (ref "C15") (pin "1") (pinfunction "1_1") (pintype "passive"))
      (node (ref "C16") (pin "1") (pinfunction "1_1") (pintype "passive"))
      (node (ref "C32") (pin "1") (pinfunction "1_1") (pintype "passive"))
      (node (ref "C33") (pin "2") (pinfunction "2_2") (pintype "passive"))
      (node (ref "C34") (pin "2") (pinfunction "2_2") (pintype "passive"))
      (node (ref "C35") (pin "1") (pinfunction "1_1") (pintype "passive"))
      (node (ref "C36") (pin "1") (pinfunction "1_1") (pintype "passive"))
      (node (ref "C37") (pin "1") (pinfunction "1_1") (pintype "passive"))
      (node (ref "D1") (pin "1") (pinfunction "K_1") (pintype "passive"))
      (node (ref "D4") (pin "1") (pinfunction "K_1") (pintype "passive"))
      (node (ref "R4") (pin "1") (pinfunction "1_1") (pintype "passive"))
      (node (ref "R54") (pin "2") (pinfunction "2_2") (pintype "passive"))
      (node (ref "R55") (pin "2") (pinfunction "2_2") (pintype "passive"))
      (node (ref "R58") (pin "2") (pinfunction "2_2") (pintype "passive"))
      (node (ref "R6") (pin "1") (pinfunction "1_1") (pintype "passive"))
      (node (ref "R7") (pin "2") (pinfunction "2_2") (pintype "passive"))
      (node (ref "U2") (pin "3") (pinfunction "VIN_3") (pintype "input"))
      (node (ref "U9") (pin "3") (pinfunction "VIN_3") (pintype "input"))
    )
    (net (code "16") (name "GND") (class "Default")
      (node (ref "C14") (pin "2") (pinfunction "2_2") (pintype "passive"))
      (node (ref "C15") (pin "2") (pinfunction "2_2") (pintype "passive"))
      (node (ref "C16") (pin "2") (pinfunction "2_2") (pintype "passive"))
      (node (ref "C17") (pin "2") (pinfunction "2_2") (pintype "passive"))
      (node (ref "C18") (pin "2") (pinfunction "2_2") (pintype "passive"))
      (node (ref "C19") (pin "2") (pinfunction "2_2") (pintype "passive"))
      (node (ref "C20") (pin "1") (pinfunction "1_1") (pintype "passive"))
      (node (ref "C21") (pin "2") (pinfunction "2_2") (pintype "passive"))
      (node (ref "C22") (pin "2") (pinfunction "2_2") (pintype "passive"))
      (node (ref "C23") (pin "2") (pinfunction "2_2") (pintype "passive"))
      (node (ref "C233") (pin "2") (pinfunction "2_2") (pintype "passive"))
      (node (ref "C24") (pin "2") (pinfunction "2_2") (pintype "passive"))
      (node (ref "C25") (pin "2") (pinfunction "2_2") (pintype "passive"))
      (node (ref "C26") (pin "2") (pinfunction "2_2") (pintype "passive"))
      (node (ref "C27") (pin "2") (pinfunction "2_2") (pintype "passive"))
      (node (ref "C28") (pin "2") (pinfunction "2_2") (pintype "passive"))
      (node (ref "C29") (pin "2") (pinfunction "2_2") (pintype "passive"))
      (node (ref "C3") (pin "2") (pinfunction "2_2") (pintype "passive"))
      (node (ref "C30") (pin "2") (pinfunction "2_2") (pintype "passive"))
      (node (ref "C32") (pin "2") (pinfunction "2_2") (pintype "passive"))
      (node (ref "C33") (pin "1") (pinfunction "1_1") (pintype "passive"))
      (node (ref "C34") (pin "1") (pinfunction "1_1") (pintype "passive"))
      (node (ref "C35") (pin "2") (pinfunction "2_2") (pintype "passive"))
      (node (ref "C36") (pin "2") (pinfunction "2_2") (pintype "passive"))
      (node (ref "C37") (pin "2") (pinfunction "2_2") (pintype "passive"))
      (node (ref "C39") (pin "2") (pinfunction "2_2") (pintype "passive"))
      (node (ref "C4") (pin "2") (pinfunction "2_2") (pintype "passive"))
      (node (ref "C40") (pin "2") (pinfunction "2_2") (pintype "passive"))
      (node (ref "C41") (pin "2") (pinfunction "2_2") (pintype "passive"))
      (node (ref "C42") (pin "2") (pinfunction "2_2") (pintype "passive"))
      (node (ref "D10") (pin "1") (pinfunction "C_1") (pintype "passive"))
      (node (ref "D4") (pin "2") (pinfunction "A_2") (pintype "passive"))
      (node (ref "D9") (pin "1") (pinfunction "C_1") (pintype "passive"))
      (node (ref "J3") (pin "2") (pinfunction "2_2") (pintype "passive"))
      (node (ref "Q1") (pin "2") (pinfunction "S_2") (pintype "passive"))
      (node (ref "Q2") (pin "2") (pinfunction "S_2") (pintype "passive"))
      (node (ref "R128") (pin "1") (pinfunction "1_1") (pintype "passive"))
      (node (ref "R135") (pin "1") (pinfunction "1_1") (pintype "passive"))
      (node (ref "R33") (pin "1") (pinfunction "1_1") (pintype "passive"))
      (node (ref "R34") (pin "1") (pinfunction "1_1") (pintype "passive"))
      (node (ref "R35") (pin "1") (pinfunction "1_1") (pintype "passive"))
      (node (ref "R39") (pin "1") (pinfunction "1_1") (pintype "passive"))
      (node (ref "R43") (pin "1") (pinfunction "1_1") (pintype "passive"))
      (node (ref "R44") (pin "1") (pinfunction "1_1") (pintype "passive"))
      (node (ref "R50") (pin "1") (pinfunction "1_1") (pintype "passive"))
      (node (ref "R52") (pin "2") (pinfunction "2_2") (pintype "passive"))
      (node (ref "T10") (pin "1") (pinfunction "1_1") (pintype "passive"))
      (node (ref "T11") (pin "1") (pinfunction "1_1") (pintype "passive"))
      (node (ref "U10") (pin "5") (pinfunction "GND_5") (pintype "passive"))
      (node (ref "U10") (pin "9") (pinfunction "EP_9") (pintype "passive"))
      (node (ref "U11") (pin "11") (pinfunction "GND_11") (pintype "power_in"))
      (node (ref "U11") (pin "12") (pinfunction "A1_12") (pintype "input"))
      (node (ref "U11") (pin "13") (pinfunction "A0_13") (pintype "input"))
      (node (ref "U11") (pin "7") (pinfunction "A2_7") (pintype "input"))
      (node (ref "U11") (pin "8") (pinfunction "VSS_8") (pintype "power_in"))
      (node (ref "U12") (pin "5") (pinfunction "GND_5") (pintype "passive"))
      (node (ref "U12") (pin "9") (pinfunction "EP_9") (pintype "passive"))
      (node (ref "U2") (pin "1") (pinfunction "GND_1") (pintype "power_in"))
      (node (ref "U7") (pin "5") (pinfunction "GND_5") (pintype "passive"))
      (node (ref "U7") (pin "9") (pinfunction "EP_9") (pintype "passive"))
      (node (ref "U8") (pin "8") (pinfunction "GND_8") (pintype "power_in"))
      (node (ref "U8") (pin "9") (pinfunction "POWERPAD_9") (pintype "power_in"))
      (node (ref "U9") (pin "1") (pinfunction "GND_1") (pintype "power_in"))
    )
    (net (code "17") (name "Net-(D1-A)") (class "Default")
      (node (ref "D1") (pin "2") (pinfunction "A_2") (pintype "passive"))
      (node (ref "J3") (pin "1") (pinfunction "1_1") (pintype "passive"))
    )
    (net (code "18") (name "Net-(D5-A)") (class "Default")
      (node (ref "D5") (pin "2") (pinfunction "A_2") (pintype "passive"))
      (node (ref "R54") (pin "1") (pinfunction "1_1") (pintype "passive"))
    )
    (net (code "19") (name "Net-(D5-C)") (class "Default")
      (node (ref "D5") (pin "1") (pinfunction "C_1") (pintype "passive"))
      (node (ref "Q1") (pin "3") (pinfunction "D_3") (pintype "passive"))
    )
    (net (code "20") (name "Net-(D6-A)") (class "Default")
      (node (ref "D6") (pin "2") (pinfunction "A_2") (pintype "passive"))
      (node (ref "R55") (pin "1") (pinfunction "1_1") (pintype "passive"))
    )
    (net (code "21") (name "Net-(D6-C)") (class "Default")
      (node (ref "D6") (pin "1") (pinfunction "C_1") (pintype "passive"))
      (node (ref "Q2") (pin "3") (pinfunction "D_3") (pintype "passive"))
    )
    (net (code "22") (name "Net-(D9-A)") (class "Default")
      (node (ref "D9") (pin "2") (pinfunction "A_2") (pintype "passive"))
      (node (ref "R58") (pin "1") (pinfunction "1_1") (pintype "passive"))
    )
    (net (code "23") (name "Net-(D10-A)") (class "Default")
      (node (ref "D10") (pin "2") (pinfunction "A_2") (pintype "passive"))
      (node (ref "R59") (pin "1") (pinfunction "1_1") (pintype "passive"))
    )
    (net (code "24") (name "Net-(Q1-G)") (class "Default")
      (node (ref "Q1") (pin "1") (pinfunction "G_1") (pintype "passive"))
      (node (ref "R60") (pin "1") (pinfunction "1_1") (pintype "passive"))
    )
    (net (code "25") (name "Net-(Q2-G)") (class "Default")
      (node (ref "Q2") (pin "1") (pinfunction "G_1") (pintype "passive"))
      (node (ref "R61") (pin "1") (pinfunction "1_1") (pintype "passive"))
    )
    (net (code "26") (name "Net-(R30-Pad1)") (class "Default")
      (node (ref "R30") (pin "1") (pinfunction "1_1") (pintype "passive"))
      (node (ref "R42") (pin "1") (pinfunction "1_1") (pintype "passive"))
      (node (ref "R44") (pin "2") (pinfunction "2_2") (pintype "passive"))
    )
    (net (code "27") (name "Net-(R40-Pad1)") (class "Default")
      (node (ref "R40") (pin "1") (pinfunction "1_1") (pintype "passive"))
      (node (ref "R46") (pin "1") (pinfunction "1_1") (pintype "passive"))
      (node (ref "T3") (pin "1") (pinfunction "1_1") (pintype "passive"))
    )
    (net (code "28") (name "Net-(R45-Pad1)") (class "Default")
      (node (ref "R45") (pin "1") (pinfunction "1_1") (pintype "passive"))
      (node (ref "R49") (pin "1") (pinfunction "1_1") (pintype "passive"))
      (node (ref "R50") (pin "2") (pinfunction "2_2") (pintype "passive"))
    )
    (net (code "29") (name "Net-(R47-Pad1)") (class "Default")
      (node (ref "R47") (pin "1") (pinfunction "1_1") (pintype "passive"))
      (node (ref "R53") (pin "1") (pinfunction "1_1") (pintype "passive"))
      (node (ref "T5") (pin "1") (pinfunction "1_1") (pintype "passive"))
    )
    (net (code "30") (name "Net-(U2-EN)") (class "Default")
      (node (ref "R4") (pin "2") (pinfunction "2_2") (pintype "passive"))
      (node (ref "U2") (pin "5") (pinfunction "EN_5") (pintype "input"))
    )
    (net (code "31") (name "Net-(U2-SW)") (class "Default")
      (node (ref "C13") (pin "1") (pinfunction "1_1") (pintype "passive"))
      (node (ref "L1") (pin "1") (pinfunction "1_1") (pintype "passive"))
      (node (ref "U2") (pin "2") (pinfunction "SW_2") (pintype "output"))
    )
    (net (code "32") (name "Net-(U2-VBST)") (class "Default")
      (node (ref "C13") (pin "2") (pinfunction "2_2") (pintype "passive"))
      (node (ref "U2") (pin "6") (pinfunction "VBST_6") (pintype "output"))
    )
    (net (code "33") (name "Net-(U2-VFB)") (class "Default")
      (node (ref "R20") (pin "1") (pinfunction "1_1") (pintype "passive"))
      (node (ref "R35") (pin "2") (pinfunction "2_2") (pintype "passive"))
      (node (ref "U2") (pin "4") (pinfunction "VFB_4") (pintype "input"))
    )
    (net (code "34") (name "Net-(U7-FB)") (class "Default")
      (node (ref "R51") (pin "1") (pinfunction "1_1") (pintype "passive"))
      (node (ref "R52") (pin "1") (pinfunction "1_1") (pintype "passive"))
      (node (ref "U7") (pin "6") (pinfunction "FB_6") (pintype "passive"))
    )
    (net (code "35") (name "Net-(U7-POK)") (class "Default")
      (node (ref "R38") (pin "2") (pinfunction "2_2") (pintype "passive"))
      (node (ref "U7") (pin "3") (pinfunction "POK_3") (pintype "passive"))
    )
    (net (code "36") (name "Net-(U8-FB)") (class "Default")
      (node (ref "R36") (pin "1") (pinfunction "1_1") (pintype "passive"))
      (node (ref "R39") (pin "2") (pinfunction "2_2") (pintype "passive"))
      (node (ref "U8") (pin "7") (pinfunction "FB_7") (pintype "input"))
    )
    (net (code "37") (name "Net-(U9-EN)") (class "Default")
      (node (ref "R6") (pin "2") (pinfunction "2_2") (pintype "passive"))
      (node (ref "U9") (pin "5") (pinfunction "EN_5") (pintype "input"))
    )
    (net (code "38") (name "Net-(U9-SW)") (class "Default")
      (node (ref "C31") (pin "2") (pinfunction "2_2") (pintype "passive"))
      (node (ref "L2") (pin "1") (pinfunction "1_1") (pintype "passive"))
      (node (ref "U9") (pin "2") (pinfunction "SW_2") (pintype "output"))
    )
    (net (code "39") (name "Net-(U9-VBST)") (class "Default")
      (node (ref "C31") (pin "1") (pinfunction "1_1") (pintype "passive"))
      (node (ref "U9") (pin "6") (pinfunction "VBST_6") (pintype "output"))
    )
    (net (code "40") (name "Net-(U9-VFB)") (class "Default")
      (node (ref "R37") (pin "2") (pinfunction "2_2") (pintype "passive"))
      (node (ref "R43") (pin "2") (pinfunction "2_2") (pintype "passive"))
      (node (ref "U9") (pin "4") (pinfunction "VFB_4") (pintype "input"))
    )
    (net (code "41") (name "Net-(U10-IN_1)") (class "Default")
      (node (ref "C27") (pin "1") (pinfunction "1_1") (pintype "passive"))
      (node (ref "C28") (pin "1") (pinfunction "1_1") (pintype "passive"))
      (node (ref "R22") (pin "2") (pinfunction "2_2") (pintype "passive"))
      (node (ref "R7") (pin "1") (pinfunction "1_1") (pintype "passive"))
      (node (ref "U10") (pin "1") (pinfunction "IN_1_1") (pintype "passive"))
      (node (ref "U10") (pin "2") (pinfunction "IN_2_2") (pintype "passive"))
    )
    (net (code "42") (name "Net-(U10-POK)") (class "Default")
      (node (ref "R41") (pin "2") (pinfunction "2_2") (pintype "passive"))
      (node (ref "U10") (pin "3") (pinfunction "POK_3") (pintype "passive"))
    )
    (net (code "43") (name "Net-(U11-HA)") (class "Default")
      (node (ref "R29") (pin "2") (pinfunction "2_2") (pintype "passive"))
      (node (ref "U11") (pin "1") (pinfunction "HA_1") (pintype "passive"))
      (node (ref "U11") (pin "3") (pinfunction "WA_3") (pintype "passive"))
    )
    (net (code "44") (name "Net-(U12-POK)") (class "Default")
      (node (ref "R48") (pin "2") (pinfunction "2_2") (pintype "passive"))
      (node (ref "U12") (pin "3") (pinfunction "POK_3") (pintype "passive"))
    )
    (net (code "45") (name "unconnected-(U8-NC_1-Pad1)") (class "Default")
      (node (ref "U8") (pin "1") (pinfunction "NC_1_1") (pintype "passive+no_connect"))
    )
    (net (code "46") (name "unconnected-(U8-NC_4-Pad4)") (class "Default")
      (node (ref "U8") (pin "4") (pinfunction "NC_4_4") (pintype "passive+no_connect"))
    )
    (net (code "47") (name "unconnected-(U8-NC_5-Pad5)") (class "Default")
      (node (ref "U8") (pin "5") (pinfunction "NC_5_5") (pintype "passive+no_connect"))
    )
  )
)
